# LNA.net
KiCad netlist of a schematic drawn in Altium Designer
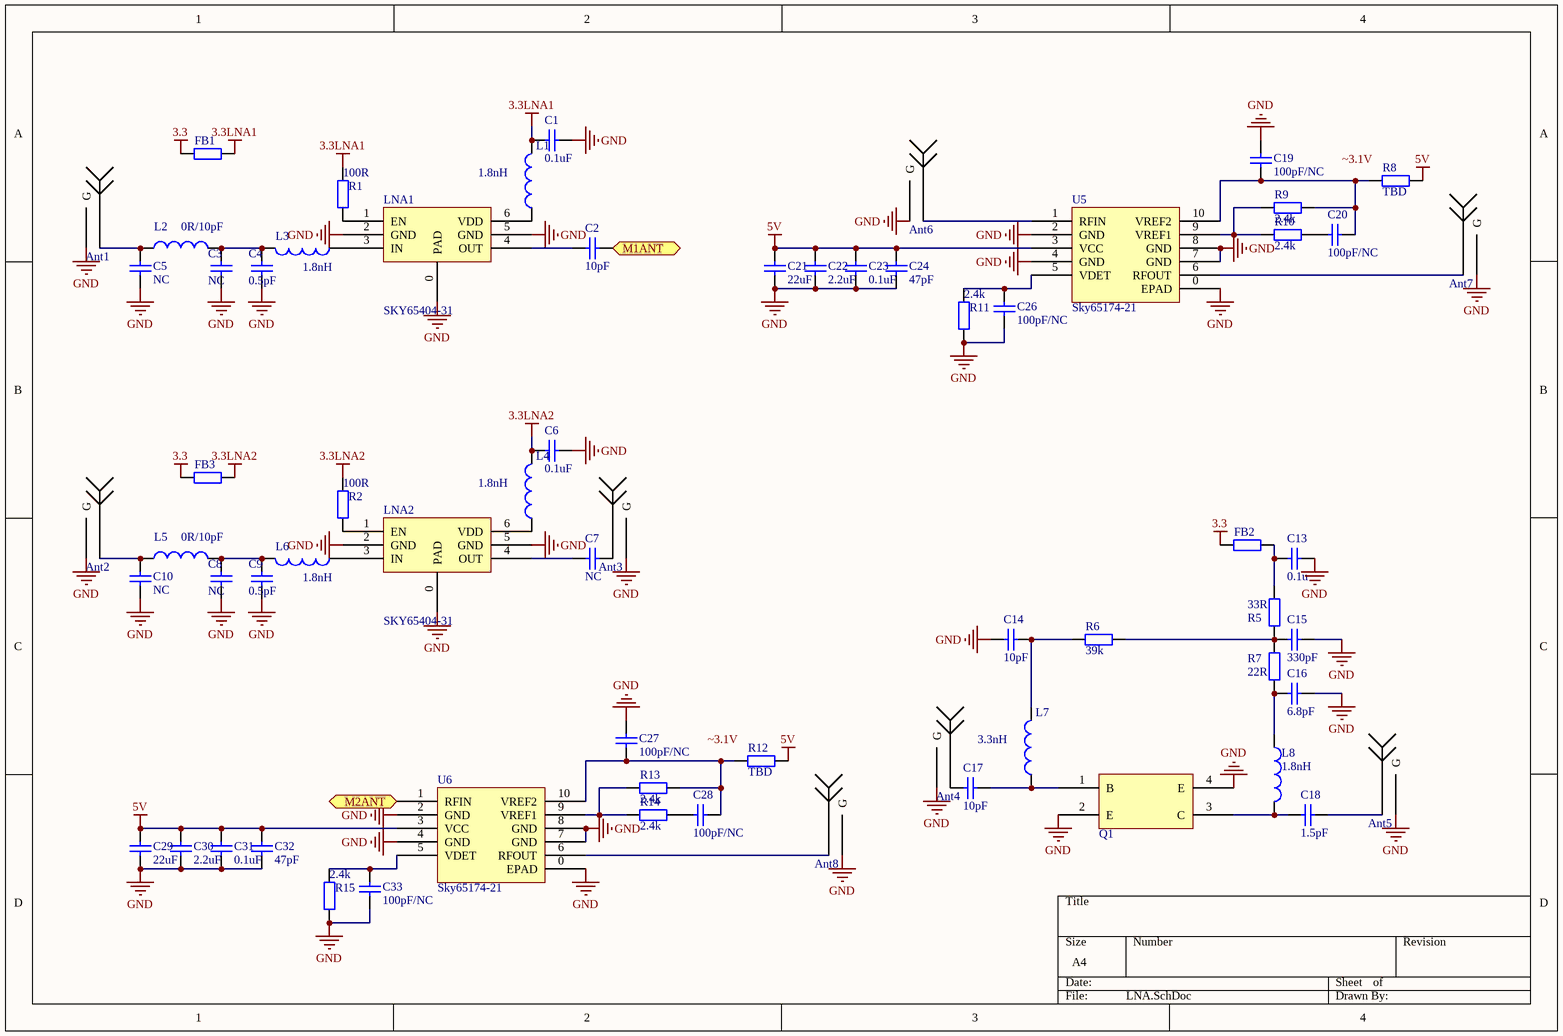
[diagram p0: LNA.SchDoc]

(export (version "E")
  (design (tool "Eeschema 10.0.6"))
  (components
    (comp (ref "Ant1") (value "Antenna") (footprint "SMA-2") (libsource (lib "RTC6705") (part "Antenna")))
    (comp (ref "Ant2") (value "Antenna") (footprint "SMA-2") (libsource (lib "RTC6705") (part "Antenna")))
    (comp (ref "Ant3") (value "Antenna") (footprint "SMA-2") (libsource (lib "RTC6705") (part "Antenna")))
    (comp (ref "Ant4") (value "Antenna") (footprint "SMA-2") (libsource (lib "RTC6705") (part "Antenna")))
    (comp (ref "Ant5") (value "Antenna") (footprint "SMA-2") (libsource (lib "RTC6705") (part "Antenna")))
    (comp (ref "Ant6") (value "Antenna") (footprint "SMA-2") (libsource (lib "RTC6705") (part "Antenna")))
    (comp (ref "Ant7") (value "Antenna") (footprint "SMA-2") (libsource (lib "RTC6705") (part "Antenna")))
    (comp (ref "Ant8") (value "Antenna") (footprint "SMA-2") (libsource (lib "RTC6705") (part "Antenna")))
    (comp (ref "C1")
      (value "0.1uF")
      (footprint "0402")
      (description "Capacitor")
      (fields (field (name "Comment") "Cap") (field (name "PUBLISHER") "Altium Limited"))
      (libsource (lib "RTC6705") (part "Cap"))
    )
    (comp (ref "C2")
      (value "10pF")
      (footprint "0402")
      (description "Capacitor")
      (fields (field (name "Comment") "Cap") (field (name "PUBLISHER") "Altium Limited"))
      (libsource (lib "RTC6705") (part "Cap"))
    )
    (comp (ref "C3")
      (value "NC")
      (footprint "0402")
      (description "Capacitor")
      (fields (field (name "Comment") "Cap") (field (name "PUBLISHER") "Altium Limited"))
      (libsource (lib "RTC6705") (part "Cap"))
    )
    (comp (ref "C4")
      (value "0.5pF")
      (footprint "0402")
      (description "Capacitor")
      (fields (field (name "Comment") "Cap") (field (name "PUBLISHER") "Altium Limited"))
      (libsource (lib "RTC6705") (part "Cap"))
    )
    (comp (ref "C5")
      (value "NC")
      (footprint "0402")
      (description "Capacitor")
      (fields (field (name "Comment") "Cap") (field (name "PUBLISHER") "Altium Limited"))
      (libsource (lib "RTC6705") (part "Cap"))
    )
    (comp (ref "C6")
      (value "0.1uF")
      (footprint "0402")
      (description "Capacitor")
      (fields (field (name "Comment") "Cap") (field (name "PUBLISHER") "Altium Limited"))
      (libsource (lib "RTC6705") (part "Cap"))
    )
    (comp (ref "C7")
      (value "NC")
      (footprint "0402")
      (description "Capacitor")
      (fields (field (name "Comment") "Cap") (field (name "PUBLISHER") "Altium Limited"))
      (libsource (lib "RTC6705") (part "Cap"))
    )
    (comp (ref "C8")
      (value "NC")
      (footprint "0402")
      (description "Capacitor")
      (fields (field (name "Comment") "Cap") (field (name "PUBLISHER") "Altium Limited"))
      (libsource (lib "RTC6705") (part "Cap"))
    )
    (comp (ref "C9")
      (value "0.5pF")
      (footprint "0402")
      (description "Capacitor")
      (fields (field (name "Comment") "Cap") (field (name "PUBLISHER") "Altium Limited"))
      (libsource (lib "RTC6705") (part "Cap"))
    )
    (comp (ref "C10")
      (value "NC")
      (footprint "0402")
      (description "Capacitor")
      (fields (field (name "Comment") "Cap") (field (name "PUBLISHER") "Altium Limited"))
      (libsource (lib "RTC6705") (part "Cap"))
    )
    (comp (ref "C13")
      (value "0.1u")
      (footprint "0402")
      (description "Capacitor")
      (fields (field (name "Comment") "Cap") (field (name "PUBLISHER") "Altium Limited"))
      (libsource (lib "RTC6705") (part "Cap"))
    )
    (comp (ref "C14")
      (value "10pF")
      (footprint "0402")
      (description "Capacitor")
      (fields (field (name "Comment") "Cap") (field (name "PUBLISHER") "Altium Limited"))
      (libsource (lib "RTC6705") (part "Cap"))
    )
    (comp (ref "C15")
      (value "330pF")
      (footprint "0402")
      (description "Capacitor")
      (fields (field (name "Comment") "Cap") (field (name "PUBLISHER") "Altium Limited"))
      (libsource (lib "RTC6705") (part "Cap"))
    )
    (comp (ref "C16")
      (value "6.8pF")
      (footprint "0402")
      (description "Capacitor")
      (fields (field (name "Comment") "Cap") (field (name "PUBLISHER") "Altium Limited"))
      (libsource (lib "RTC6705") (part "Cap"))
    )
    (comp (ref "C17")
      (value "10pF")
      (footprint "0402")
      (description "Capacitor")
      (fields (field (name "Comment") "Cap") (field (name "PUBLISHER") "Altium Limited"))
      (libsource (lib "RTC6705") (part "Cap"))
    )
    (comp (ref "C18")
      (value "1.5pF")
      (footprint "0402")
      (description "Capacitor")
      (fields (field (name "Comment") "Cap") (field (name "PUBLISHER") "Altium Limited"))
      (libsource (lib "RTC6705") (part "Cap"))
    )
    (comp (ref "C19")
      (value "100pF/NC")
      (footprint "0402")
      (description "Capacitor")
      (fields (field (name "Comment") "Cap") (field (name "PUBLISHER") "Altium Limited"))
      (libsource (lib "RTC6705") (part "Cap"))
    )
    (comp (ref "C20")
      (value "100pF/NC")
      (footprint "0402")
      (description "Capacitor")
      (fields (field (name "Comment") "Cap") (field (name "PUBLISHER") "Altium Limited"))
      (libsource (lib "RTC6705") (part "Cap"))
    )
    (comp (ref "C21")
      (value "22uF")
      (footprint "0805")
      (description "Capacitor")
      (fields (field (name "Comment") "Cap") (field (name "PUBLISHER") "Altium Limited"))
      (libsource (lib "RTC6705") (part "Cap"))
    )
    (comp (ref "C22")
      (value "2.2uF")
      (footprint "0603")
      (description "Capacitor")
      (fields (field (name "Comment") "Cap") (field (name "PUBLISHER") "Altium Limited"))
      (libsource (lib "RTC6705") (part "Cap"))
    )
    (comp (ref "C23")
      (value "0.1uF")
      (footprint "0402")
      (description "Capacitor")
      (fields (field (name "Comment") "Cap") (field (name "PUBLISHER") "Altium Limited"))
      (libsource (lib "RTC6705") (part "Cap"))
    )
    (comp (ref "C24")
      (value "47pF")
      (footprint "0402")
      (description "Capacitor")
      (fields (field (name "Comment") "Cap") (field (name "PUBLISHER") "Altium Limited"))
      (libsource (lib "RTC6705") (part "Cap"))
    )
    (comp (ref "C26")
      (value "100pF/NC")
      (footprint "0402")
      (description "Capacitor")
      (fields (field (name "Comment") "Cap") (field (name "PUBLISHER") "Altium Limited"))
      (libsource (lib "RTC6705") (part "Cap"))
    )
    (comp (ref "C27")
      (value "100pF/NC")
      (footprint "0402")
      (description "Capacitor")
      (fields (field (name "Comment") "Cap") (field (name "PUBLISHER") "Altium Limited"))
      (libsource (lib "RTC6705") (part "Cap"))
    )
    (comp (ref "C28")
      (value "100pF/NC")
      (footprint "0402")
      (description "Capacitor")
      (fields (field (name "Comment") "Cap") (field (name "PUBLISHER") "Altium Limited"))
      (libsource (lib "RTC6705") (part "Cap"))
    )
    (comp (ref "C29")
      (value "22uF")
      (footprint "0805")
      (description "Capacitor")
      (fields (field (name "Comment") "Cap") (field (name "PUBLISHER") "Altium Limited"))
      (libsource (lib "RTC6705") (part "Cap"))
    )
    (comp (ref "C30")
      (value "2.2uF")
      (footprint "0603")
      (description "Capacitor")
      (fields (field (name "Comment") "Cap") (field (name "PUBLISHER") "Altium Limited"))
      (libsource (lib "RTC6705") (part "Cap"))
    )
    (comp (ref "C31")
      (value "0.1uF")
      (footprint "0402")
      (description "Capacitor")
      (fields (field (name "Comment") "Cap") (field (name "PUBLISHER") "Altium Limited"))
      (libsource (lib "RTC6705") (part "Cap"))
    )
    (comp (ref "C32")
      (value "47pF")
      (footprint "0402")
      (description "Capacitor")
      (fields (field (name "Comment") "Cap") (field (name "PUBLISHER") "Altium Limited"))
      (libsource (lib "RTC6705") (part "Cap"))
    )
    (comp (ref "C33")
      (value "100pF/NC")
      (footprint "0402")
      (description "Capacitor")
      (fields (field (name "Comment") "Cap") (field (name "PUBLISHER") "Altium Limited"))
      (libsource (lib "RTC6705") (part "Cap"))
    )
    (comp (ref "FB1")
      (value "Res2")
      (footprint "0402")
      (description "Resistor")
      (fields (field (name "PUBLISHER") "Altium Limited"))
      (libsource (lib "") (part "Res2_3"))
    )
    (comp (ref "FB2")
      (value "Res2")
      (footprint "0402")
      (description "Resistor")
      (fields (field (name "PUBLISHER") "Altium Limited"))
      (libsource (lib "") (part "Res2_3"))
    )
    (comp (ref "FB3")
      (value "Res2")
      (footprint "0402")
      (description "Resistor")
      (fields (field (name "PUBLISHER") "Altium Limited"))
      (libsource (lib "") (part "Res2_3"))
    )
    (comp (ref "L1")
      (value "1.8nH")
      (footprint "0402")
      (description "Inductor")
      (fields (field (name "PUBLISHER") "Altium Limited"))
      (libsource (lib "Miscellaneous Devices") (part "Inductor"))
    )
    (comp (ref "L2")
      (value "0R/10pF")
      (footprint "0402")
      (description "Inductor")
      (fields (field (name "PUBLISHER") "Altium Limited"))
      (libsource (lib "Miscellaneous Devices") (part "Inductor"))
    )
    (comp (ref "L3")
      (value "1.8nH")
      (footprint "0402")
      (description "Inductor")
      (fields (field (name "PUBLISHER") "Altium Limited"))
      (libsource (lib "Miscellaneous Devices") (part "Inductor"))
    )
    (comp (ref "L4")
      (value "1.8nH")
      (footprint "0402")
      (description "Inductor")
      (fields (field (name "PUBLISHER") "Altium Limited"))
      (libsource (lib "Miscellaneous Devices") (part "Inductor"))
    )
    (comp (ref "L5")
      (value "0R/10pF")
      (footprint "0402")
      (description "Inductor")
      (fields (field (name "PUBLISHER") "Altium Limited"))
      (libsource (lib "Miscellaneous Devices") (part "Inductor"))
    )
    (comp (ref "L6")
      (value "1.8nH")
      (footprint "0402")
      (description "Inductor")
      (fields (field (name "PUBLISHER") "Altium Limited"))
      (libsource (lib "Miscellaneous Devices") (part "Inductor"))
    )
    (comp (ref "L7")
      (value "3.3nH")
      (footprint "0402")
      (description "Inductor")
      (fields (field (name "PUBLISHER") "Altium Limited"))
      (libsource (lib "Miscellaneous Devices") (part "Inductor"))
    )
    (comp (ref "L8")
      (value "1.8nH")
      (footprint "0402")
      (description "Inductor")
      (fields (field (name "PUBLISHER") "Altium Limited"))
      (libsource (lib "Miscellaneous Devices") (part "Inductor"))
    )
    (comp (ref "LNA1")
      (value "SKY65404-31")
      (footprint "SKY65404-31")
      (libsource (lib "BK5811") (part "SKY65404-31"))
    )
    (comp (ref "LNA2")
      (value "SKY65404-31")
      (footprint "SKY65404-31")
      (libsource (lib "BK5811") (part "SKY65404-31"))
    )
    (comp (ref "Q1") (value "RF_BJT") (footprint "SOT343-4(RF)") (libsource (lib "WifiGain") (part "RF_BJT")))
    (comp (ref "R1")
      (value "100R")
      (footprint "0402")
      (description "Resistor")
      (fields (field (name "Comment") "Res2") (field (name "PUBLISHER") "Altium Limited"))
      (libsource (lib "") (part "Res2_1"))
    )
    (comp (ref "R2")
      (value "100R")
      (footprint "0402")
      (description "Resistor")
      (fields (field (name "Comment") "Res2") (field (name "PUBLISHER") "Altium Limited"))
      (libsource (lib "") (part "Res2_1"))
    )
    (comp (ref "R5")
      (value "33R")
      (footprint "0402")
      (description "Resistor")
      (fields (field (name "Comment") "Res2") (field (name "PUBLISHER") "Altium Limited"))
      (libsource (lib "") (part "Res2_1"))
    )
    (comp (ref "R6")
      (value "39k")
      (footprint "0402")
      (description "Resistor")
      (fields (field (name "Comment") "Res2") (field (name "PUBLISHER") "Altium Limited"))
      (libsource (lib "RTC6705") (part "Res2"))
    )
    (comp (ref "R7")
      (value "22R")
      (footprint "0402")
      (description "Resistor")
      (fields (field (name "Comment") "Res2") (field (name "PUBLISHER") "Altium Limited"))
      (libsource (lib "") (part "Res2_2"))
    )
    (comp (ref "R8")
      (value "TBD")
      (footprint "0402")
      (description "Resistor")
      (fields (field (name "Comment") "Res2") (field (name "PUBLISHER") "Altium Limited"))
      (libsource (lib "RTC6705") (part "Res2"))
    )
    (comp (ref "R9")
      (value "2.4k")
      (footprint "0402")
      (description "Resistor")
      (fields (field (name "Comment") "Res2") (field (name "PUBLISHER") "Altium Limited"))
      (libsource (lib "RTC6705") (part "Res2"))
    )
    (comp (ref "R10")
      (value "2.4k")
      (footprint "0402")
      (description "Resistor")
      (fields (field (name "Comment") "Res2") (field (name "PUBLISHER") "Altium Limited"))
      (libsource (lib "RTC6705") (part "Res2"))
    )
    (comp (ref "R11")
      (value "2.4k")
      (footprint "0402")
      (description "Resistor")
      (fields (field (name "Comment") "Res2") (field (name "PUBLISHER") "Altium Limited"))
      (libsource (lib "") (part "Res2_1"))
    )
    (comp (ref "R12")
      (value "TBD")
      (footprint "0402")
      (description "Resistor")
      (fields (field (name "Comment") "Res2") (field (name "PUBLISHER") "Altium Limited"))
      (libsource (lib "RTC6705") (part "Res2"))
    )
    (comp (ref "R13")
      (value "2.4k")
      (footprint "0402")
      (description "Resistor")
      (fields (field (name "Comment") "Res2") (field (name "PUBLISHER") "Altium Limited"))
      (libsource (lib "RTC6705") (part "Res2"))
    )
    (comp (ref "R14")
      (value "2.4k")
      (footprint "0402")
      (description "Resistor")
      (fields (field (name "Comment") "Res2") (field (name "PUBLISHER") "Altium Limited"))
      (libsource (lib "RTC6705") (part "Res2"))
    )
    (comp (ref "R15")
      (value "2.4k")
      (footprint "0402")
      (description "Resistor")
      (fields (field (name "Comment") "Res2") (field (name "PUBLISHER") "Altium Limited"))
      (libsource (lib "") (part "Res2_1"))
    )
    (comp (ref "U5")
      (value "Sky65174-21")
      (footprint "SKY65174-21")
      (libsource (lib "WifiGain") (part "Sky65174-21"))
    )
    (comp (ref "U6")
      (value "Sky65174-21")
      (footprint "SKY65174-21")
      (libsource (lib "WifiGain") (part "Sky65174-21"))
    )
  )
  (nets
    (net (code "1") (name "/M1ANT") (class "Default")
      (node (ref "C2") (pin "2") (pinfunction "2_2") (pintype "passive"))
    )
    (net (code "2") (name "/M2ANT") (class "Default")
      (node (ref "U6") (pin "1") (pinfunction "RFIN_1") (pintype "passive"))
    )
    (net (code "4") (name "3.3") (class "Default")
      (node (ref "FB1") (pin "1") (pinfunction "1_1") (pintype "passive"))
      (node (ref "FB2") (pin "1") (pinfunction "1_1") (pintype "passive"))
      (node (ref "FB3") (pin "1") (pinfunction "1_1") (pintype "passive"))
    )
    (net (code "5") (name "3.3LNA1") (class "Default")
      (node (ref "C1") (pin "2") (pinfunction "2_2") (pintype "passive"))
      (node (ref "FB1") (pin "2") (pinfunction "2_2") (pintype "passive"))
      (node (ref "L1") (pin "2") (pinfunction "2_2") (pintype "passive"))
      (node (ref "R1") (pin "2") (pinfunction "2_2") (pintype "passive"))
    )
    (net (code "6") (name "3.3LNA2") (class "Default")
      (node (ref "C6") (pin "2") (pinfunction "2_2") (pintype "passive"))
      (node (ref "FB3") (pin "2") (pinfunction "2_2") (pintype "passive"))
      (node (ref "L4") (pin "2") (pinfunction "2_2") (pintype "passive"))
      (node (ref "R2") (pin "2") (pinfunction "2_2") (pintype "passive"))
    )
    (net (code "7") (name "5V") (class "Default")
      (node (ref "C21") (pin "1") (pinfunction "1_1") (pintype "passive"))
      (node (ref "C22") (pin "1") (pinfunction "1_1") (pintype "passive"))
      (node (ref "C23") (pin "1") (pinfunction "1_1") (pintype "passive"))
      (node (ref "C24") (pin "1") (pinfunction "1_1") (pintype "passive"))
      (node (ref "C29") (pin "1") (pinfunction "1_1") (pintype "passive"))
      (node (ref "C30") (pin "1") (pinfunction "1_1") (pintype "passive"))
      (node (ref "C31") (pin "1") (pinfunction "1_1") (pintype "passive"))
      (node (ref "C32") (pin "1") (pinfunction "1_1") (pintype "passive"))
      (node (ref "R12") (pin "1") (pinfunction "1_1") (pintype "passive"))
      (node (ref "R8") (pin "1") (pinfunction "1_1") (pintype "passive"))
      (node (ref "U5") (pin "3") (pinfunction "VCC_3") (pintype "passive"))
      (node (ref "U6") (pin "3") (pinfunction "VCC_3") (pintype "passive"))
    )
    (net (code "8") (name "GND") (class "Default")
      (node (ref "Ant1") (pin "GND") (pinfunction "G_GND") (pintype "passive"))
      (node (ref "Ant2") (pin "GND") (pinfunction "G_GND") (pintype "passive"))
      (node (ref "Ant3") (pin "GND") (pinfunction "G_GND") (pintype "passive"))
      (node (ref "Ant4") (pin "GND") (pinfunction "G_GND") (pintype "passive"))
      (node (ref "Ant5") (pin "GND") (pinfunction "G_GND") (pintype "passive"))
      (node (ref "Ant6") (pin "GND") (pinfunction "G_GND") (pintype "passive"))
      (node (ref "Ant7") (pin "GND") (pinfunction "G_GND") (pintype "passive"))
      (node (ref "Ant8") (pin "GND") (pinfunction "G_GND") (pintype "passive"))
      (node (ref "C1") (pin "1") (pinfunction "1_1") (pintype "passive"))
      (node (ref "C10") (pin "1") (pinfunction "1_1") (pintype "passive"))
      (node (ref "C13") (pin "1") (pinfunction "1_1") (pintype "passive"))
      (node (ref "C14") (pin "2") (pinfunction "2_2") (pintype "passive"))
      (node (ref "C15") (pin "2") (pinfunction "2_2") (pintype "passive"))
      (node (ref "C16") (pin "1") (pinfunction "1_1") (pintype "passive"))
      (node (ref "C19") (pin "1") (pinfunction "1_1") (pintype "passive"))
      (node (ref "C21") (pin "2") (pinfunction "2_2") (pintype "passive"))
      (node (ref "C22") (pin "2") (pinfunction "2_2") (pintype "passive"))
      (node (ref "C23") (pin "2") (pinfunction "2_2") (pintype "passive"))
      (node (ref "C24") (pin "2") (pinfunction "2_2") (pintype "passive"))
      (node (ref "C26") (pin "2") (pinfunction "2_2") (pintype "passive"))
      (node (ref "C27") (pin "1") (pinfunction "1_1") (pintype "passive"))
      (node (ref "C29") (pin "2") (pinfunction "2_2") (pintype "passive"))
      (node (ref "C3") (pin "1") (pinfunction "1_1") (pintype "passive"))
      (node (ref "C30") (pin "2") (pinfunction "2_2") (pintype "passive"))
      (node (ref "C31") (pin "2") (pinfunction "2_2") (pintype "passive"))
      (node (ref "C32") (pin "2") (pinfunction "2_2") (pintype "passive"))
      (node (ref "C33") (pin "2") (pinfunction "2_2") (pintype "passive"))
      (node (ref "C4") (pin "1") (pinfunction "1_1") (pintype "passive"))
      (node (ref "C5") (pin "1") (pinfunction "1_1") (pintype "passive"))
      (node (ref "C6") (pin "1") (pinfunction "1_1") (pintype "passive"))
      (node (ref "C8") (pin "1") (pinfunction "1_1") (pintype "passive"))
      (node (ref "C9") (pin "1") (pinfunction "1_1") (pintype "passive"))
      (node (ref "LNA1") (pin "0") (pinfunction "PAD_0") (pintype "passive"))
      (node (ref "LNA1") (pin "2") (pinfunction "GND_2") (pintype "passive"))
      (node (ref "LNA1") (pin "5") (pinfunction "GND_5") (pintype "passive"))
      (node (ref "LNA2") (pin "0") (pinfunction "PAD_0") (pintype "passive"))
      (node (ref "LNA2") (pin "2") (pinfunction "GND_2") (pintype "passive"))
      (node (ref "LNA2") (pin "5") (pinfunction "GND_5") (pintype "passive"))
      (node (ref "Q1") (pin "2") (pinfunction "E_2") (pintype "passive"))
      (node (ref "Q1") (pin "4") (pinfunction "E_4") (pintype "passive"))
      (node (ref "R11") (pin "1") (pinfunction "1_1") (pintype "passive"))
      (node (ref "R15") (pin "1") (pinfunction "1_1") (pintype "passive"))
      (node (ref "U5") (pin "0") (pinfunction "EPAD_0") (pintype "passive"))
      (node (ref "U5") (pin "2") (pinfunction "GND_2") (pintype "passive"))
      (node (ref "U5") (pin "4") (pinfunction "GND_4") (pintype "passive"))
      (node (ref "U5") (pin "7") (pinfunction "GND_7") (pintype "passive"))
      (node (ref "U5") (pin "8") (pinfunction "GND_8") (pintype "passive"))
      (node (ref "U6") (pin "0") (pinfunction "EPAD_0") (pintype "passive"))
      (node (ref "U6") (pin "2") (pinfunction "GND_2") (pintype "passive"))
      (node (ref "U6") (pin "4") (pinfunction "GND_4") (pintype "passive"))
      (node (ref "U6") (pin "7") (pinfunction "GND_7") (pintype "passive"))
      (node (ref "U6") (pin "8") (pinfunction "GND_8") (pintype "passive"))
    )
    (net (code "9") (name "Net-(Ant1-Pad1)") (class "Default")
      (node (ref "Ant1") (pin "1") (pinfunction "1_1") (pintype "passive"))
      (node (ref "C5") (pin "2") (pinfunction "2_2") (pintype "passive"))
      (node (ref "L2") (pin "1") (pinfunction "1_1") (pintype "passive"))
    )
    (net (code "10") (name "Net-(Ant2-Pad1)") (class "Default")
      (node (ref "Ant2") (pin "1") (pinfunction "1_1") (pintype "passive"))
      (node (ref "C10") (pin "2") (pinfunction "2_2") (pintype "passive"))
      (node (ref "L5") (pin "1") (pinfunction "1_1") (pintype "passive"))
    )
    (net (code "11") (name "Net-(Ant3-Pad1)") (class "Default")
      (node (ref "Ant3") (pin "1") (pinfunction "1_1") (pintype "passive"))
      (node (ref "C7") (pin "2") (pinfunction "2_2") (pintype "passive"))
    )
    (net (code "12") (name "Net-(Ant4-Pad1)") (class "Default")
      (node (ref "Ant4") (pin "1") (pinfunction "1_1") (pintype "passive"))
      (node (ref "C17") (pin "2") (pinfunction "2_2") (pintype "passive"))
    )
    (net (code "13") (name "Net-(Ant5-Pad1)") (class "Default")
      (node (ref "Ant5") (pin "1") (pinfunction "1_1") (pintype "passive"))
      (node (ref "C18") (pin "1") (pinfunction "1_1") (pintype "passive"))
    )
    (net (code "14") (name "Net-(C3-Pad2)") (class "Default")
      (node (ref "C3") (pin "2") (pinfunction "2_2") (pintype "passive"))
      (node (ref "C4") (pin "2") (pinfunction "2_2") (pintype "passive"))
      (node (ref "L2") (pin "2") (pinfunction "2_2") (pintype "passive"))
      (node (ref "L3") (pin "2") (pinfunction "2_2") (pintype "passive"))
    )
    (net (code "15") (name "Net-(C8-Pad2)") (class "Default")
      (node (ref "C8") (pin "2") (pinfunction "2_2") (pintype "passive"))
      (node (ref "C9") (pin "2") (pinfunction "2_2") (pintype "passive"))
      (node (ref "L5") (pin "2") (pinfunction "2_2") (pintype "passive"))
      (node (ref "L6") (pin "2") (pinfunction "2_2") (pintype "passive"))
    )
    (net (code "16") (name "Net-(C13-Pad2)") (class "Default")
      (node (ref "C13") (pin "2") (pinfunction "2_2") (pintype "passive"))
      (node (ref "FB2") (pin "2") (pinfunction "2_2") (pintype "passive"))
      (node (ref "R5") (pin "2") (pinfunction "2_2") (pintype "passive"))
    )
    (net (code "17") (name "Net-(C14-Pad1)") (class "Default")
      (node (ref "C14") (pin "1") (pinfunction "1_1") (pintype "passive"))
      (node (ref "L7") (pin "2") (pinfunction "2_2") (pintype "passive"))
      (node (ref "R6") (pin "2") (pinfunction "2_2") (pintype "passive"))
    )
    (net (code "18") (name "Net-(C15-Pad1)") (class "Default")
      (node (ref "C15") (pin "1") (pinfunction "1_1") (pintype "passive"))
      (node (ref "R5") (pin "1") (pinfunction "1_1") (pintype "passive"))
      (node (ref "R6") (pin "1") (pinfunction "1_1") (pintype "passive"))
      (node (ref "R7") (pin "1") (pinfunction "1_1") (pintype "passive"))
    )
    (net (code "19") (name "Net-(C16-Pad2)") (class "Default")
      (node (ref "C16") (pin "2") (pinfunction "2_2") (pintype "passive"))
      (node (ref "L8") (pin "1") (pinfunction "1_1") (pintype "passive"))
      (node (ref "R7") (pin "2") (pinfunction "2_2") (pintype "passive"))
    )
    (net (code "20") (name "Net-(C20-Pad1)") (class "Default")
      (node (ref "C20") (pin "1") (pinfunction "1_1") (pintype "passive"))
      (node (ref "R10") (pin "1") (pinfunction "1_1") (pintype "passive"))
    )
    (net (code "21") (name "Net-(C28-Pad1)") (class "Default")
      (node (ref "C28") (pin "1") (pinfunction "1_1") (pintype "passive"))
      (node (ref "R14") (pin "1") (pinfunction "1_1") (pintype "passive"))
    )
    (net (code "22") (name "Net-(LNA1-EN)") (class "Default")
      (node (ref "LNA1") (pin "1") (pinfunction "EN_1") (pintype "passive"))
      (node (ref "R1") (pin "1") (pinfunction "1_1") (pintype "passive"))
    )
    (net (code "23") (name "Net-(LNA1-IN)") (class "Default")
      (node (ref "L3") (pin "1") (pinfunction "1_1") (pintype "passive"))
      (node (ref "LNA1") (pin "3") (pinfunction "IN_3") (pintype "passive"))
    )
    (net (code "24") (name "Net-(LNA1-OUT)") (class "Default")
      (node (ref "C2") (pin "1") (pinfunction "1_1") (pintype "passive"))
      (node (ref "LNA1") (pin "4") (pinfunction "OUT_4") (pintype "passive"))
    )
    (net (code "25") (name "Net-(LNA1-VDD)") (class "Default")
      (node (ref "L1") (pin "1") (pinfunction "1_1") (pintype "passive"))
      (node (ref "LNA1") (pin "6") (pinfunction "VDD_6") (pintype "passive"))
    )
    (net (code "26") (name "Net-(LNA2-EN)") (class "Default")
      (node (ref "LNA2") (pin "1") (pinfunction "EN_1") (pintype "passive"))
      (node (ref "R2") (pin "1") (pinfunction "1_1") (pintype "passive"))
    )
    (net (code "27") (name "Net-(LNA2-IN)") (class "Default")
      (node (ref "L6") (pin "1") (pinfunction "1_1") (pintype "passive"))
      (node (ref "LNA2") (pin "3") (pinfunction "IN_3") (pintype "passive"))
    )
    (net (code "28") (name "Net-(LNA2-OUT)") (class "Default")
      (node (ref "C7") (pin "1") (pinfunction "1_1") (pintype "passive"))
      (node (ref "LNA2") (pin "4") (pinfunction "OUT_4") (pintype "passive"))
    )
    (net (code "29") (name "Net-(LNA2-VDD)") (class "Default")
      (node (ref "L4") (pin "1") (pinfunction "1_1") (pintype "passive"))
      (node (ref "LNA2") (pin "6") (pinfunction "VDD_6") (pintype "passive"))
    )
    (net (code "30") (name "Net-(Q1-B)") (class "Default")
      (node (ref "C17") (pin "1") (pinfunction "1_1") (pintype "passive"))
      (node (ref "L7") (pin "1") (pinfunction "1_1") (pintype "passive"))
      (node (ref "Q1") (pin "1") (pinfunction "B_1") (pintype "passive"))
    )
    (net (code "31") (name "Net-(Q1-C)") (class "Default")
      (node (ref "C18") (pin "2") (pinfunction "2_2") (pintype "passive"))
      (node (ref "L8") (pin "2") (pinfunction "2_2") (pintype "passive"))
      (node (ref "Q1") (pin "3") (pinfunction "C_3") (pintype "passive"))
    )
    (net (code "32") (name "Net-(U5-RFIN)") (class "Default")
      (node (ref "Ant6") (pin "1") (pinfunction "1_1") (pintype "passive"))
      (node (ref "U5") (pin "1") (pinfunction "RFIN_1") (pintype "passive"))
    )
    (net (code "33") (name "Net-(U5-RFOUT)") (class "Default")
      (node (ref "Ant7") (pin "1") (pinfunction "1_1") (pintype "passive"))
      (node (ref "U5") (pin "6") (pinfunction "RFOUT_6") (pintype "passive"))
    )
    (net (code "34") (name "Net-(U5-VDET)") (class "Default")
      (node (ref "C26") (pin "1") (pinfunction "1_1") (pintype "passive"))
      (node (ref "R11") (pin "2") (pinfunction "2_2") (pintype "passive"))
      (node (ref "U5") (pin "5") (pinfunction "VDET_5") (pintype "passive"))
    )
    (net (code "35") (name "Net-(U5-VREF1)") (class "Default")
      (node (ref "R10") (pin "2") (pinfunction "2_2") (pintype "passive"))
      (node (ref "R9") (pin "2") (pinfunction "2_2") (pintype "passive"))
      (node (ref "U5") (pin "9") (pinfunction "VREF1_9") (pintype "passive"))
    )
    (net (code "36") (name "Net-(U5-VREF2)") (class "Default")
      (node (ref "C19") (pin "2") (pinfunction "2_2") (pintype "passive"))
      (node (ref "C20") (pin "2") (pinfunction "2_2") (pintype "passive"))
      (node (ref "R8") (pin "2") (pinfunction "2_2") (pintype "passive"))
      (node (ref "R9") (pin "1") (pinfunction "1_1") (pintype "passive"))
      (node (ref "U5") (pin "10") (pinfunction "VREF2_10") (pintype "passive"))
    )
    (net (code "37") (name "Net-(U6-RFOUT)") (class "Default")
      (node (ref "Ant8") (pin "1") (pinfunction "1_1") (pintype "passive"))
      (node (ref "U6") (pin "6") (pinfunction "RFOUT_6") (pintype "passive"))
    )
    (net (code "38") (name "Net-(U6-VDET)") (class "Default")
      (node (ref "C33") (pin "1") (pinfunction "1_1") (pintype "passive"))
      (node (ref "R15") (pin "2") (pinfunction "2_2") (pintype "passive"))
      (node (ref "U6") (pin "5") (pinfunction "VDET_5") (pintype "passive"))
    )
    (net (code "39") (name "Net-(U6-VREF1)") (class "Default")
      (node (ref "R13") (pin "2") (pinfunction "2_2") (pintype "passive"))
      (node (ref "R14") (pin "2") (pinfunction "2_2") (pintype "passive"))
      (node (ref "U6") (pin "9") (pinfunction "VREF1_9") (pintype "passive"))
    )
    (net (code "40") (name "Net-(U6-VREF2)") (class "Default")
      (node (ref "C27") (pin "2") (pinfunction "2_2") (pintype "passive"))
      (node (ref "C28") (pin "2") (pinfunction "2_2") (pintype "passive"))
      (node (ref "R12") (pin "2") (pinfunction "2_2") (pintype "passive"))
      (node (ref "R13") (pin "1") (pinfunction "1_1") (pintype "passive"))
      (node (ref "U6") (pin "10") (pinfunction "VREF2_10") (pintype "passive"))
    )
  )
)
